# Rear_left_lamp_v3B.net
KiCad netlist of a schematic drawn in EAGLE
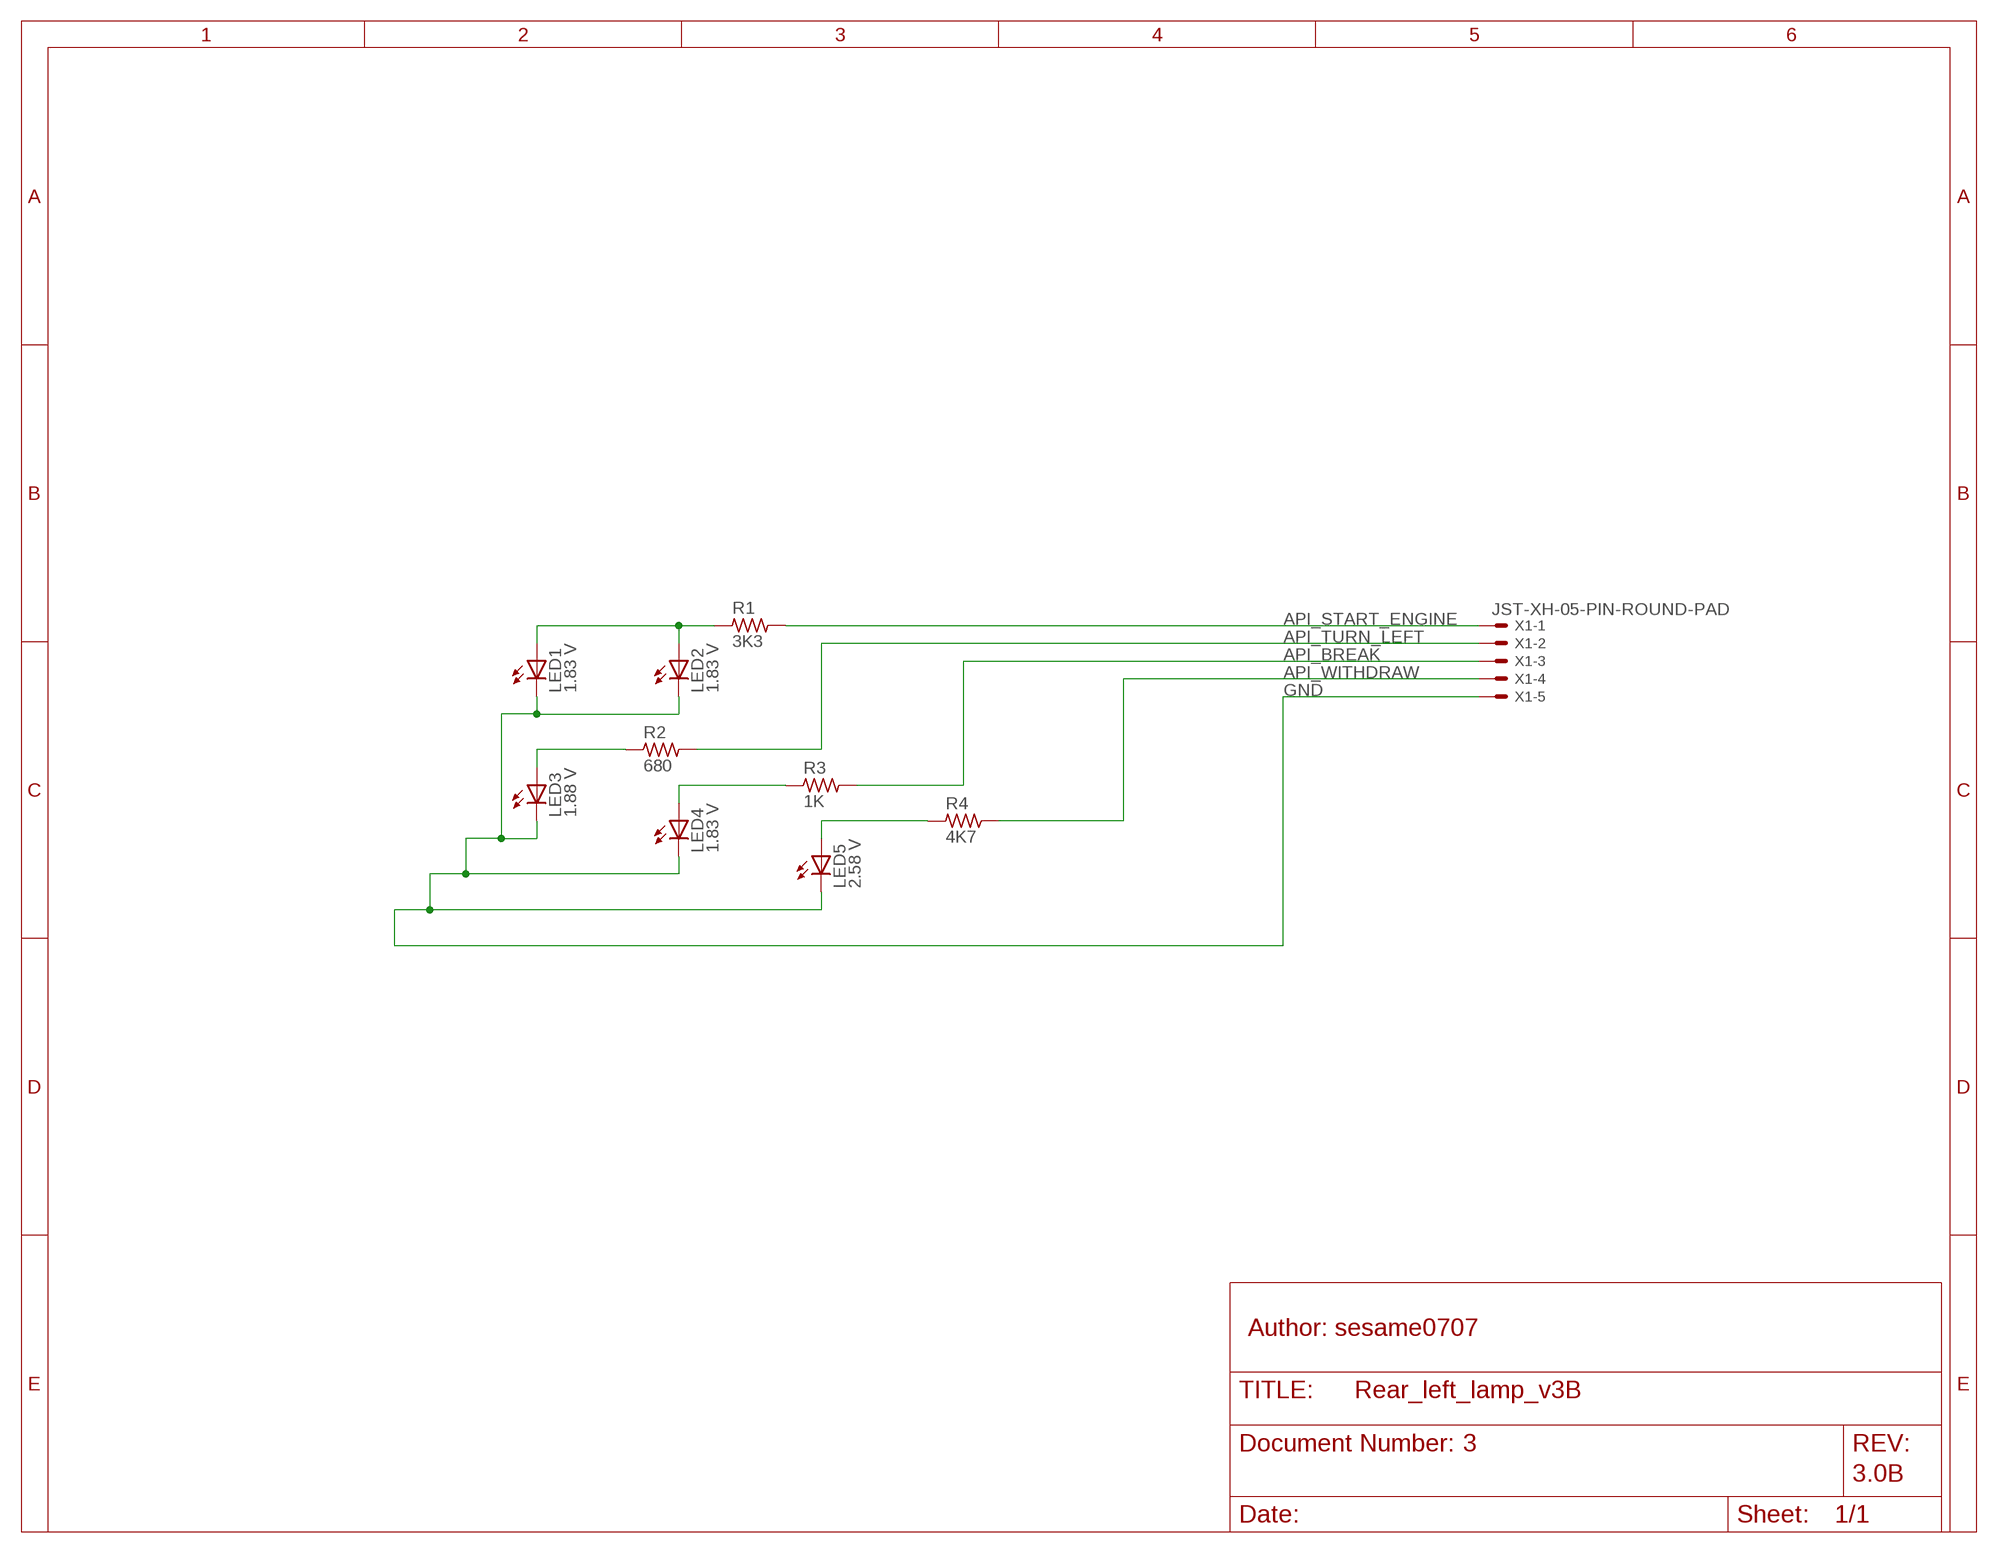
[diagram p0: schematic, sheet 1]

(export (version "E")
  (design (tool "Eeschema 10.0.6"))
  (components
    (comp (ref "LED1")
      (value "1.83 V")
      (footprint "eagle-import:LED5MM")
      (libsource (lib "eagle-import") (part "LED5MM"))
    )
    (comp (ref "LED2")
      (value "1.83 V")
      (footprint "eagle-import:LED5MM")
      (libsource (lib "eagle-import") (part "LED5MM"))
    )
    (comp (ref "LED3")
      (value "1.88 V")
      (footprint "eagle-import:LED5MM")
      (libsource (lib "eagle-import") (part "LED5MM"))
    )
    (comp (ref "LED4")
      (value "1.83 V")
      (footprint "eagle-import:LED5MM")
      (libsource (lib "eagle-import") (part "LED5MM"))
    )
    (comp (ref "LED5")
      (value "2.58 V")
      (footprint "eagle-import:LED5MM")
      (libsource (lib "eagle-import") (part "LED5MM"))
    )
    (comp (ref "R1")
      (value "3K3")
      (footprint "eagle-import:R1206")
      (libsource (lib "eagle-import") (part "R_1206"))
    )
    (comp (ref "R2")
      (value "680")
      (footprint "eagle-import:R1206")
      (libsource (lib "eagle-import") (part "R_1206"))
    )
    (comp (ref "R3")
      (value "1K")
      (footprint "eagle-import:R1206")
      (libsource (lib "eagle-import") (part "R_1206"))
    )
    (comp (ref "R4")
      (value "4K7")
      (footprint "eagle-import:R1206")
      (libsource (lib "eagle-import") (part "R_1206"))
    )
    (comp (ref "X1")
      (value "JST-XH-05-PIN-ROUND-PAD")
      (footprint "eagle-import:JST-XH-05-PACKAGE-ROUND-PAD")
      (libsource (lib "eagle-import") (part "JST-XH-05-PIN-ROUND-PAD"))
    )
  )
  (nets
    (net (code "1") (name "/API_BREAK") (class "Default")
      (node (ref "R3") (pin "2") (pinfunction "2_2") (pintype "passive"))
      (node (ref "X1") (pin "3") (pinfunction "S_3") (pintype "passive"))
    )
    (net (code "2") (name "/API_START_ENGINE") (class "Default")
      (node (ref "LED1") (pin "A") (pinfunction "A_A") (pintype "passive"))
      (node (ref "LED2") (pin "A") (pinfunction "A_A") (pintype "passive"))
      (node (ref "R1") (pin "1") (pinfunction "1_1") (pintype "passive"))
    )
    (net (code "3") (name "/API_TURN_LEFT") (class "Default")
      (node (ref "R2") (pin "2") (pinfunction "2_2") (pintype "passive"))
      (node (ref "X1") (pin "2") (pinfunction "S_2") (pintype "passive"))
    )
    (net (code "4") (name "/API_WITHDRAW") (class "Default")
      (node (ref "R4") (pin "2") (pinfunction "2_2") (pintype "passive"))
      (node (ref "X1") (pin "4") (pinfunction "S_4") (pintype "passive"))
    )
    (net (code "5") (name "/GND") (class "Default")
      (node (ref "LED1") (pin "K") (pinfunction "C_K") (pintype "passive"))
      (node (ref "LED2") (pin "K") (pinfunction "C_K") (pintype "passive"))
      (node (ref "LED3") (pin "K") (pinfunction "C_K") (pintype "passive"))
      (node (ref "LED4") (pin "K") (pinfunction "C_K") (pintype "passive"))
      (node (ref "LED5") (pin "K") (pinfunction "C_K") (pintype "passive"))
      (node (ref "X1") (pin "5") (pinfunction "S_5") (pintype "passive"))
    )
    (net (code "6") (name "Net-(LED3-PadA)") (class "Default")
      (node (ref "LED3") (pin "A") (pinfunction "A_A") (pintype "passive"))
      (node (ref "R2") (pin "1") (pinfunction "1_1") (pintype "passive"))
    )
    (net (code "7") (name "Net-(LED4-PadA)") (class "Default")
      (node (ref "LED4") (pin "A") (pinfunction "A_A") (pintype "passive"))
      (node (ref "R3") (pin "1") (pinfunction "1_1") (pintype "passive"))
    )
    (net (code "8") (name "Net-(LED5-PadA)") (class "Default")
      (node (ref "LED5") (pin "A") (pinfunction "A_A") (pintype "passive"))
      (node (ref "R4") (pin "1") (pinfunction "1_1") (pintype "passive"))
    )
    (net (code "9") (name "Net-(X1A-S)") (class "Default")
      (node (ref "R1") (pin "2") (pinfunction "2_2") (pintype "passive"))
      (node (ref "X1") (pin "1") (pinfunction "S_1") (pintype "passive"))
    )
  )
)
